# batteryholder2S3P.net
KiCad netlist of a schematic drawn in EAGLE
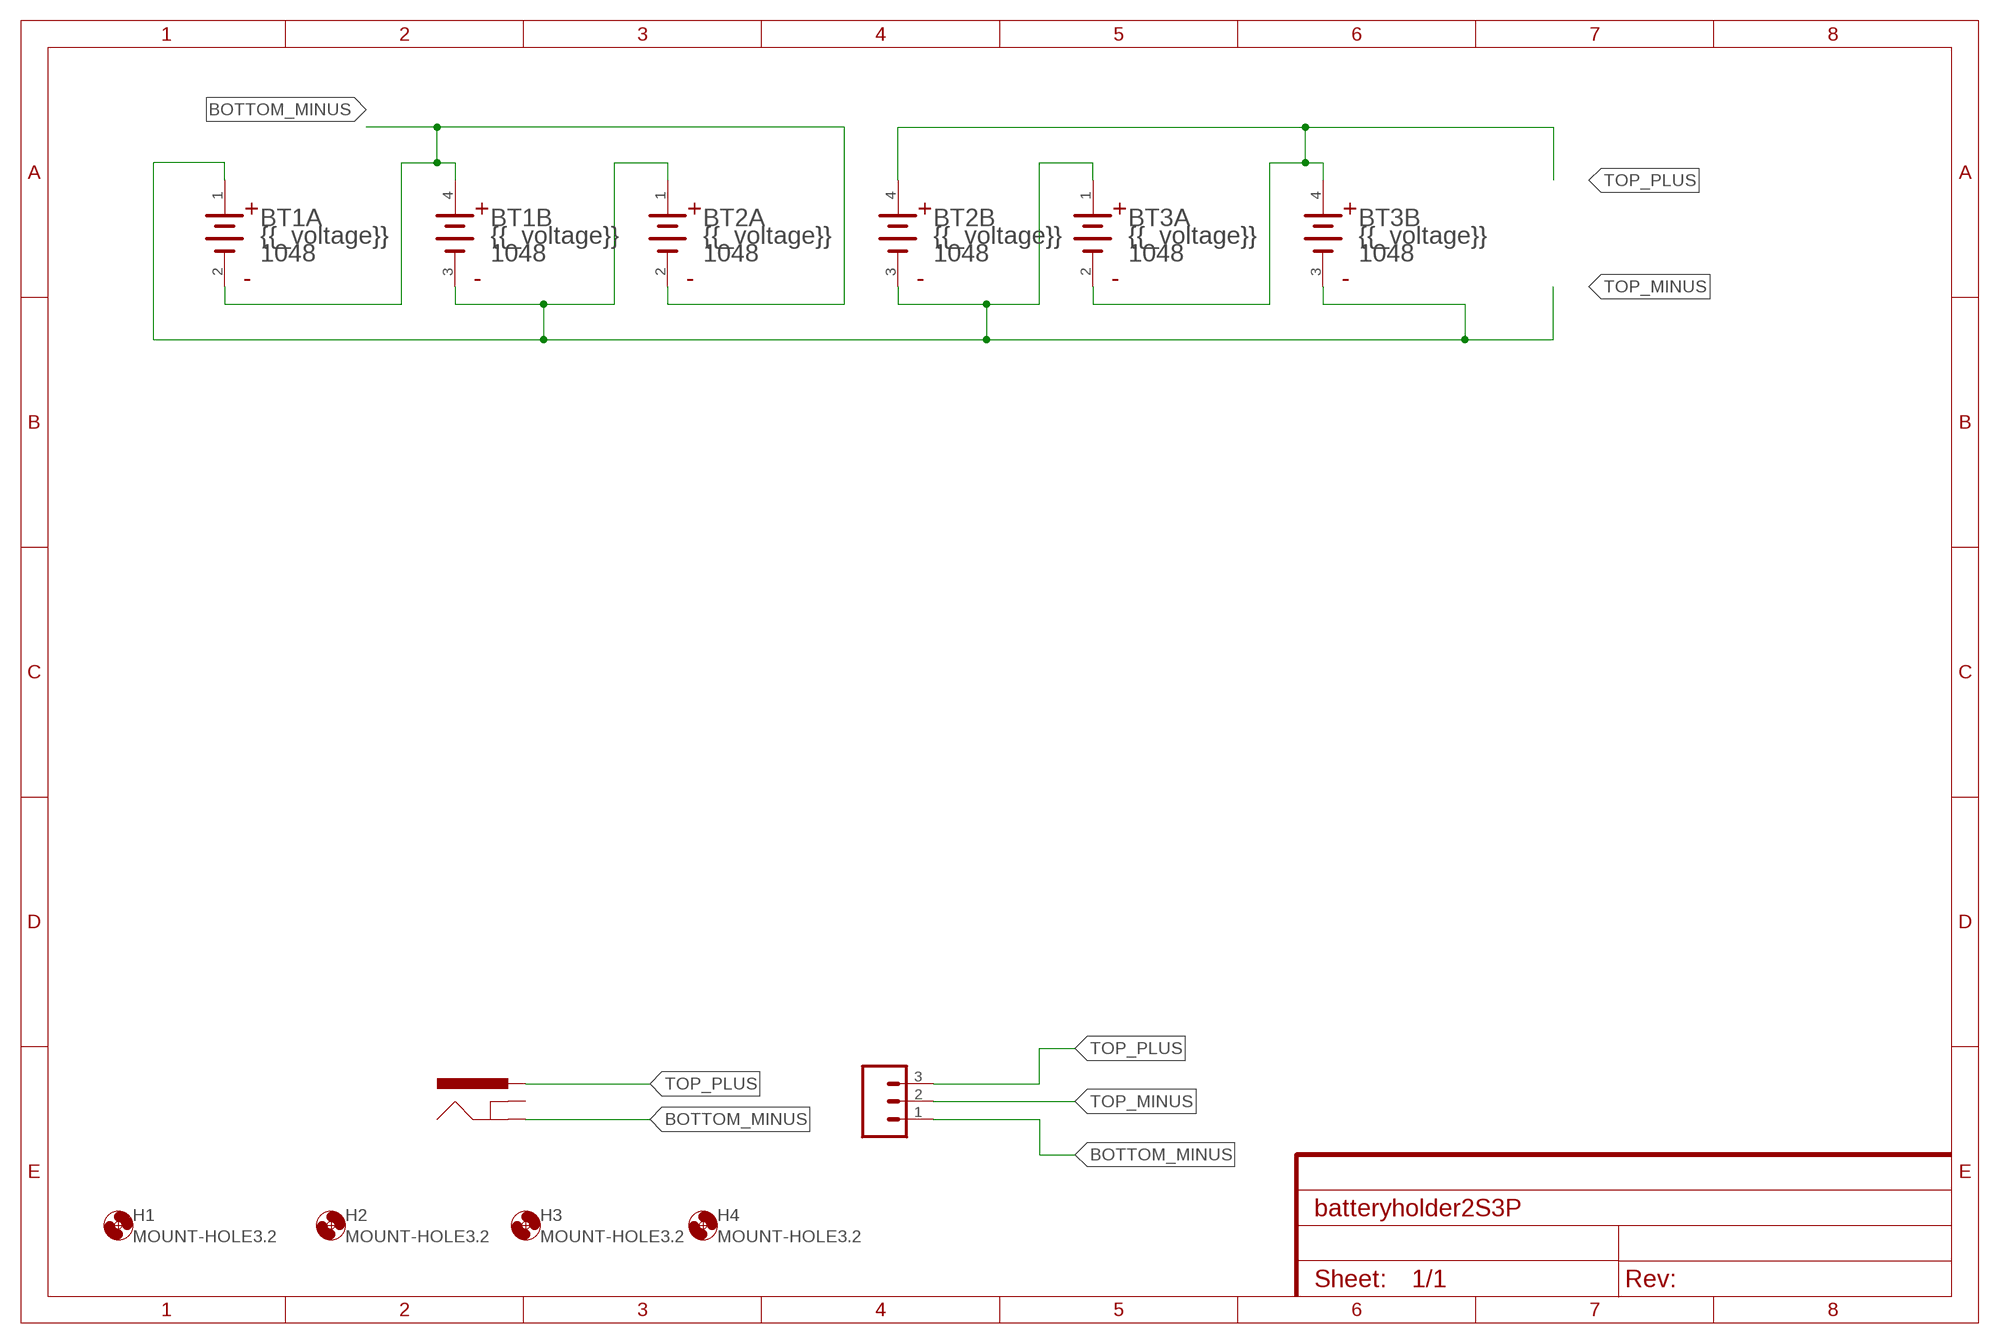
[diagram p0: schematic, sheet 1]

(export (version "E")
  (design (tool "Eeschema 10.0.6"))
  (components
    (comp (ref "BT1")
      (value "KEYSTONE_1048KEYSTONE_1048_0_0")
      (footprint "eagle-import:KEYSTONE_1048_0")
      (fields
        (field (name "DIGIKEY_PART_NUMBER") "36-1048-ND")
        (field (name "MF") "Keystone")
        (field (name "MOUSER_PART_NUMBER") "534-1048")
      )
      (libsource (lib "eagle-import") (part "KEYSTONE_1048KEYSTONE_1048_0_0"))
    )
    (comp (ref "BT2")
      (value "KEYSTONE_1048KEYSTONE_1048_0_0")
      (footprint "eagle-import:KEYSTONE_1048_0")
      (fields
        (field (name "DIGIKEY_PART_NUMBER") "36-1048-ND")
        (field (name "MF") "Keystone")
        (field (name "MOUSER_PART_NUMBER") "534-1048")
      )
      (libsource (lib "eagle-import") (part "KEYSTONE_1048KEYSTONE_1048_0_0"))
    )
    (comp (ref "BT3")
      (value "KEYSTONE_1048KEYSTONE_1048_0_0")
      (footprint "eagle-import:KEYSTONE_1048_0")
      (fields
        (field (name "DIGIKEY_PART_NUMBER") "36-1048-ND")
        (field (name "MF") "Keystone")
        (field (name "MOUSER_PART_NUMBER") "534-1048")
      )
      (libsource (lib "eagle-import") (part "KEYSTONE_1048KEYSTONE_1048_0_0"))
    )
    (comp (ref "H1")
      (value "MOUNT-HOLE3.2")
      (footprint "eagle-import:3,2")
      (libsource (lib "eagle-import") (part "MOUNT-HOLE3.2"))
    )
    (comp (ref "H2")
      (value "MOUNT-HOLE3.2")
      (footprint "eagle-import:3,2")
      (libsource (lib "eagle-import") (part "MOUNT-HOLE3.2"))
    )
    (comp (ref "H3")
      (value "MOUNT-HOLE3.2")
      (footprint "eagle-import:3,2")
      (libsource (lib "eagle-import") (part "MOUNT-HOLE3.2"))
    )
    (comp (ref "H4")
      (value "MOUNT-HOLE3.2")
      (footprint "eagle-import:3,2")
      (libsource (lib "eagle-import") (part "MOUNT-HOLE3.2"))
    )
    (comp (ref "J1")
      (value "CONN_03-SCREW-5MM")
      (footprint "eagle-import:SCREWTERMINAL-5MM-3")
      (libsource (lib "eagle-import") (part "CONN_03-SCREW-5MM"))
    )
    (comp (ref "J3")
      (value "5.5x2.1mm Barrel")
      (footprint "eagle-import:POWER_JACK_SMD")
      (libsource (lib "eagle-import") (part "POWER_JACKSMD"))
    )
  )
  (nets
    (net (code "1") (name "BOTTOM_MINUS") (class "Default")
      (node (ref "BT1") (pin "2") (pinfunction "1_CATHODE_2") (pintype "passive"))
      (node (ref "BT1") (pin "4") (pinfunction "2_ANODE_4") (pintype "passive"))
      (node (ref "BT2") (pin "2") (pinfunction "1_CATHODE_2") (pintype "passive"))
      (node (ref "J1") (pin "1") (pinfunction "1_1") (pintype "passive"))
      (node (ref "J3") (pin "P$4") (pinfunction "GND_P$4") (pintype "bidirectional"))
    )
    (net (code "2") (name "TOP_MINUS") (class "Default")
      (node (ref "BT1") (pin "1") (pinfunction "1_ANODE_1") (pintype "passive"))
      (node (ref "BT1") (pin "3") (pinfunction "2_CATHODE_3") (pintype "passive"))
      (node (ref "BT2") (pin "1") (pinfunction "1_ANODE_1") (pintype "passive"))
      (node (ref "BT2") (pin "3") (pinfunction "2_CATHODE_3") (pintype "passive"))
      (node (ref "BT3") (pin "1") (pinfunction "1_ANODE_1") (pintype "passive"))
      (node (ref "BT3") (pin "3") (pinfunction "2_CATHODE_3") (pintype "passive"))
      (node (ref "J1") (pin "2") (pinfunction "2_2") (pintype "passive"))
    )
    (net (code "3") (name "TOP_PLUS") (class "Default")
      (node (ref "BT2") (pin "4") (pinfunction "2_ANODE_4") (pintype "passive"))
      (node (ref "BT3") (pin "2") (pinfunction "1_CATHODE_2") (pintype "passive"))
      (node (ref "BT3") (pin "4") (pinfunction "2_ANODE_4") (pintype "passive"))
      (node (ref "J1") (pin "3") (pinfunction "3_3") (pintype "passive"))
      (node (ref "J3") (pin "VIN0") (pinfunction "PWR_VIN0") (pintype "bidirectional"))
    )
    (net (code "4") (name "unconnected-(J3-GNDBREAK-PadGND)") (class "Default")
      (node (ref "J3") (pin "GND") (pinfunction "GNDBREAK_GND") (pintype "bidirectional"))
    )
  )
)
